# EC_Shield.net
KiCad netlist of a schematic drawn in EAGLE
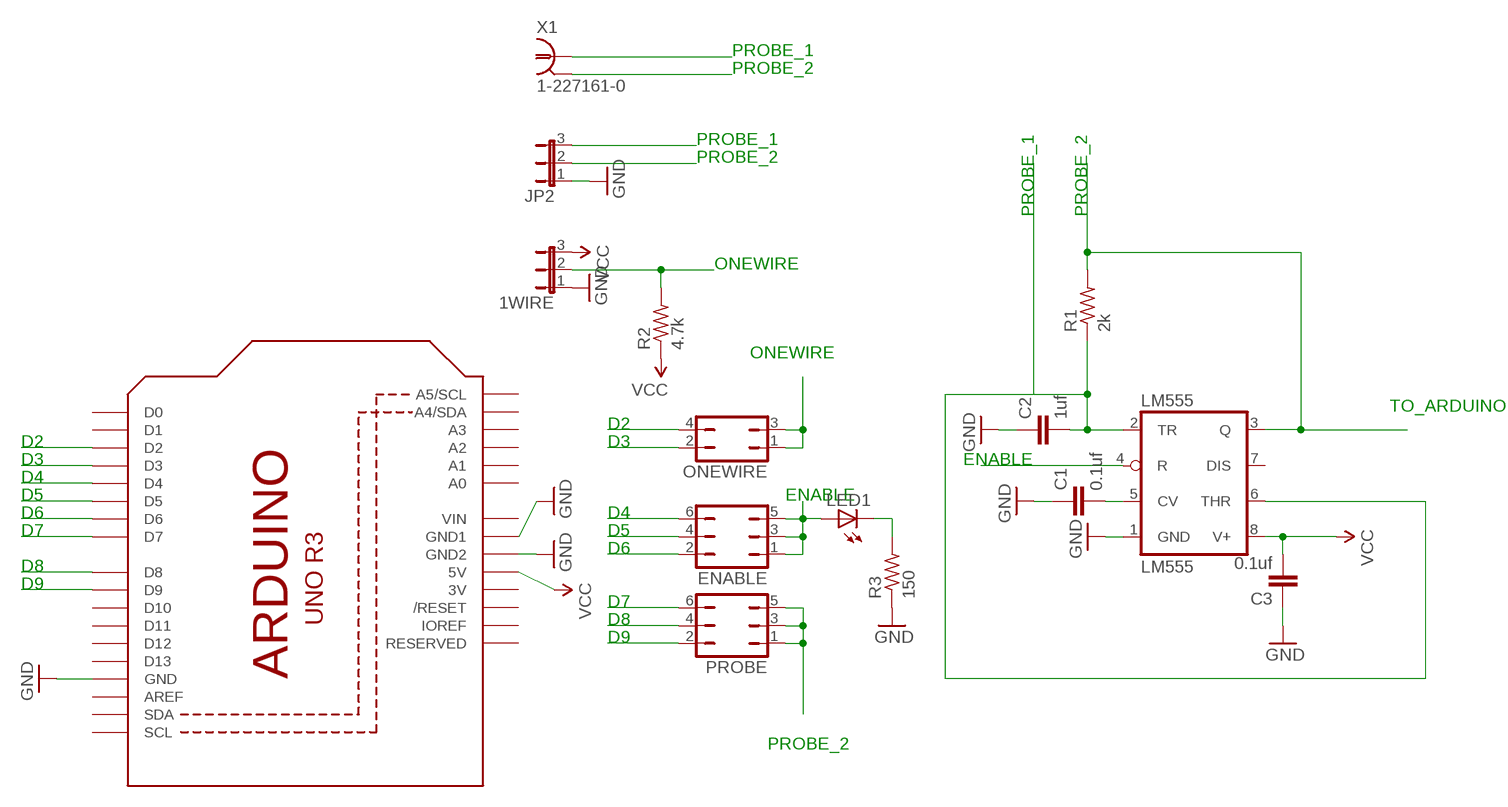
[diagram p0: schematic, sheet 1]

(export (version "E")
  (design (tool "Eeschema 10.0.6"))
  (components
    (comp (ref "1WIRE")
      (value "JP2E")
      (footprint "eagle-import:JP2")
      (libsource (lib "eagle-import") (part "JP2E"))
    )
    (comp (ref "C1")
      (value "0.1uf")
      (footprint "eagle-import:C0603")
      (libsource (lib "eagle-import") (part "C-EUC0603"))
    )
    (comp (ref "C2")
      (value "1uf")
      (footprint "eagle-import:C0603")
      (libsource (lib "eagle-import") (part "C-EUC0603"))
    )
    (comp (ref "C3")
      (value "0.1uf")
      (footprint "eagle-import:C0603")
      (libsource (lib "eagle-import") (part "C-EUC0603"))
    )
    (comp (ref "ENABLE")
      (value "JP3Q")
      (footprint "eagle-import:JP3Q")
      (libsource (lib "eagle-import") (part "JP3Q"))
    )
    (comp (ref "JP2")
      (value "JP2E")
      (footprint "eagle-import:JP2")
      (libsource (lib "eagle-import") (part "JP2E"))
    )
    (comp (ref "LED1")
      (value "LED0603")
      (footprint "eagle-import:LED-0603")
      (libsource (lib "eagle-import") (part "LED0603"))
    )
    (comp (ref "LM555")
      (value "LM555")
      (footprint "eagle-import:SO08")
      (libsource (lib "eagle-import") (part "555DLM"))
    )
    (comp (ref "ONEWIRE")
      (value "JP2Q")
      (footprint "eagle-import:JP2Q")
      (libsource (lib "eagle-import") (part "JP2Q"))
    )
    (comp (ref "PROBE")
      (value "JP3Q")
      (footprint "eagle-import:JP3Q")
      (libsource (lib "eagle-import") (part "JP3Q"))
    )
    (comp (ref "R1")
      (value "2k")
      (footprint "eagle-import:R0603")
      (libsource (lib "eagle-import") (part "R-US_R0603"))
    )
    (comp (ref "R2")
      (value "4.7k")
      (footprint "eagle-import:R0603")
      (libsource (lib "eagle-import") (part "R-US_R0603"))
    )
    (comp (ref "R3")
      (value "150")
      (footprint "eagle-import:R0603")
      (libsource (lib "eagle-import") (part "R-US_R0603"))
    )
    (comp (ref "U2")
      (value "ARDUINOR3-DIMENSION")
      (footprint "eagle-import:ARDUINOR3")
      (libsource (lib "eagle-import") (part "ARDUINOR3-DIMENSION"))
    )
    (comp (ref "X1")
      (value "1-227161-0")
      (footprint "eagle-import:AMP_227161")
      (libsource (lib "eagle-import") (part "?2271611--0"))
    )
  )
  (nets
    (net (code "1") (name "/3V") (class "Default")
      (node (ref "U2") (pin "3V") (pinfunction "3V_3V") (pintype "power_in"))
    )
    (net (code "2") (name "/D2") (class "Default")
      (node (ref "ONEWIRE") (pin "4") (pinfunction "4_4") (pintype "passive"))
      (node (ref "U2") (pin "D2") (pinfunction "D2_D2") (pintype "bidirectional"))
    )
    (net (code "3") (name "/D3") (class "Default")
      (node (ref "ONEWIRE") (pin "2") (pinfunction "2_2") (pintype "passive"))
      (node (ref "U2") (pin "D3") (pinfunction "D3_D3") (pintype "bidirectional"))
    )
    (net (code "4") (name "/D4") (class "Default")
      (node (ref "ENABLE") (pin "6") (pinfunction "6_6") (pintype "passive"))
      (node (ref "U2") (pin "D4") (pinfunction "D4_D4") (pintype "bidirectional"))
    )
    (net (code "5") (name "/D5") (class "Default")
      (node (ref "ENABLE") (pin "4") (pinfunction "4_4") (pintype "passive"))
      (node (ref "U2") (pin "D5") (pinfunction "D5_D5") (pintype "bidirectional"))
    )
    (net (code "6") (name "/D6") (class "Default")
      (node (ref "ENABLE") (pin "2") (pinfunction "2_2") (pintype "passive"))
      (node (ref "U2") (pin "D6") (pinfunction "D6_D6") (pintype "bidirectional"))
    )
    (net (code "7") (name "/D7") (class "Default")
      (node (ref "PROBE") (pin "6") (pinfunction "6_6") (pintype "passive"))
      (node (ref "U2") (pin "D7") (pinfunction "D7_D7") (pintype "bidirectional"))
    )
    (net (code "8") (name "/D8") (class "Default")
      (node (ref "PROBE") (pin "4") (pinfunction "4_4") (pintype "passive"))
      (node (ref "U2") (pin "D8") (pinfunction "D8_D8") (pintype "bidirectional"))
    )
    (net (code "9") (name "/D9") (class "Default")
      (node (ref "PROBE") (pin "2") (pinfunction "2_2") (pintype "passive"))
      (node (ref "U2") (pin "D9") (pinfunction "D9_D9") (pintype "bidirectional"))
    )
    (net (code "10") (name "/ENABLE") (class "Default")
      (node (ref "ENABLE") (pin "1") (pinfunction "1_1") (pintype "passive"))
      (node (ref "ENABLE") (pin "3") (pinfunction "3_3") (pintype "passive"))
      (node (ref "ENABLE") (pin "5") (pinfunction "5_5") (pintype "passive"))
      (node (ref "LED1") (pin "A") (pinfunction "A_A") (pintype "passive"))
      (node (ref "LM555") (pin "4") (pinfunction "R_4") (pintype "input"))
    )
    (net (code "11") (name "/ONEWIRE") (class "Default")
      (node (ref "1WIRE") (pin "2") (pinfunction "2_2") (pintype "passive"))
      (node (ref "ONEWIRE") (pin "1") (pinfunction "1_1") (pintype "passive"))
      (node (ref "ONEWIRE") (pin "3") (pinfunction "3_3") (pintype "passive"))
      (node (ref "R2") (pin "2") (pinfunction "2_2") (pintype "passive"))
    )
    (net (code "12") (name "/PROBE_1") (class "Default")
      (node (ref "C2") (pin "2") (pinfunction "2_2") (pintype "passive"))
      (node (ref "JP2") (pin "3") (pinfunction "3_3") (pintype "passive"))
      (node (ref "LM555") (pin "2") (pinfunction "TR_2") (pintype "input"))
      (node (ref "LM555") (pin "6") (pinfunction "THR_6") (pintype "input"))
      (node (ref "R1") (pin "1") (pinfunction "1_1") (pintype "passive"))
      (node (ref "X1") (pin "1") (pinfunction "1_1") (pintype "passive"))
    )
    (net (code "13") (name "/PROBE_2") (class "Default")
      (node (ref "JP2") (pin "2") (pinfunction "2_2") (pintype "passive"))
      (node (ref "LM555") (pin "3") (pinfunction "Q_3") (pintype "output"))
      (node (ref "PROBE") (pin "1") (pinfunction "1_1") (pintype "passive"))
      (node (ref "PROBE") (pin "3") (pinfunction "3_3") (pintype "passive"))
      (node (ref "PROBE") (pin "5") (pinfunction "5_5") (pintype "passive"))
      (node (ref "R1") (pin "2") (pinfunction "2_2") (pintype "passive"))
      (node (ref "X1") (pin "2") (pinfunction "GND_2") (pintype "power_in"))
    )
    (net (code "14") (name "/VIN") (class "Default")
      (node (ref "U2") (pin "VIN") (pinfunction "VIN_VIN") (pintype "power_in"))
    )
    (net (code "15") (name "GND") (class "Default")
      (node (ref "1WIRE") (pin "1") (pinfunction "1_1") (pintype "passive"))
      (node (ref "C1") (pin "1") (pinfunction "1_1") (pintype "passive"))
      (node (ref "C2") (pin "1") (pinfunction "1_1") (pintype "passive"))
      (node (ref "C3") (pin "1") (pinfunction "1_1") (pintype "passive"))
      (node (ref "JP2") (pin "1") (pinfunction "1_1") (pintype "passive"))
      (node (ref "LM555") (pin "1") (pinfunction "GND_1") (pintype "power_in"))
      (node (ref "R3") (pin "1") (pinfunction "1_1") (pintype "passive"))
      (node (ref "U2") (pin "GND") (pinfunction "GND_GND") (pintype "power_in"))
      (node (ref "U2") (pin "GND1") (pinfunction "GND1_GND1") (pintype "power_in"))
      (node (ref "U2") (pin "GND2") (pinfunction "GND2_GND2") (pintype "power_in"))
    )
    (net (code "16") (name "Net-(LED1-PadC)") (class "Default")
      (node (ref "LED1") (pin "C") (pinfunction "C_C") (pintype "passive"))
      (node (ref "R3") (pin "2") (pinfunction "2_2") (pintype "passive"))
    )
    (net (code "17") (name "Net-(LM555-CV)") (class "Default")
      (node (ref "C1") (pin "2") (pinfunction "2_2") (pintype "passive"))
      (node (ref "LM555") (pin "5") (pinfunction "CV_5") (pintype "input"))
    )
    (net (code "18") (name "VCC") (class "Default")
      (node (ref "1WIRE") (pin "3") (pinfunction "3_3") (pintype "passive"))
      (node (ref "C3") (pin "2") (pinfunction "2_2") (pintype "passive"))
      (node (ref "LM555") (pin "8") (pinfunction "V+_8") (pintype "power_in"))
      (node (ref "R2") (pin "1") (pinfunction "1_1") (pintype "passive"))
      (node (ref "U2") (pin "5V") (pinfunction "5V_5V") (pintype "power_in"))
    )
    (net (code "19") (name "unconnected-(LM555-DIS-Pad7)") (class "Default")
      (node (ref "LM555") (pin "7") (pinfunction "DIS_7") (pintype "input"))
    )
    (net (code "20") (name "unconnected-(U2-A4{slash}SDA-PadA4)") (class "Default")
      (node (ref "U2") (pin "A4") (pinfunction "A4/SDA_A4") (pintype "bidirectional"))
    )
    (net (code "21") (name "unconnected-(U2-A5{slash}SCL-PadA5)") (class "Default")
      (node (ref "U2") (pin "A5") (pinfunction "A5/SCL_A5") (pintype "bidirectional"))
    )
    (net (code "22") (name "unconnected-(U2-PadA0)") (class "Default")
      (node (ref "U2") (pin "A0") (pinfunction "A0_A0") (pintype "bidirectional"))
    )
    (net (code "23") (name "unconnected-(U2-PadA1)") (class "Default")
      (node (ref "U2") (pin "A1") (pinfunction "A1_A1") (pintype "bidirectional"))
    )
    (net (code "24") (name "unconnected-(U2-PadA2)") (class "Default")
      (node (ref "U2") (pin "A2") (pinfunction "A2_A2") (pintype "bidirectional"))
    )
    (net (code "25") (name "unconnected-(U2-PadA3)") (class "Default")
      (node (ref "U2") (pin "A3") (pinfunction "A3_A3") (pintype "bidirectional"))
    )
    (net (code "26") (name "unconnected-(U2-PadAREF)") (class "Default")
      (node (ref "U2") (pin "AREF") (pinfunction "AREF_AREF") (pintype "bidirectional"))
    )
    (net (code "27") (name "unconnected-(U2-PadD0)") (class "Default")
      (node (ref "U2") (pin "D0") (pinfunction "D0_D0") (pintype "bidirectional"))
    )
    (net (code "28") (name "unconnected-(U2-PadD1)") (class "Default")
      (node (ref "U2") (pin "D1") (pinfunction "D1_D1") (pintype "bidirectional"))
    )
    (net (code "29") (name "unconnected-(U2-PadD10)") (class "Default")
      (node (ref "U2") (pin "D10") (pinfunction "D10_D10") (pintype "bidirectional"))
    )
    (net (code "30") (name "unconnected-(U2-PadD11)") (class "Default")
      (node (ref "U2") (pin "D11") (pinfunction "D11_D11") (pintype "bidirectional"))
    )
    (net (code "31") (name "unconnected-(U2-PadD12)") (class "Default")
      (node (ref "U2") (pin "D12") (pinfunction "D12_D12") (pintype "bidirectional"))
    )
    (net (code "32") (name "unconnected-(U2-PadD13)") (class "Default")
      (node (ref "U2") (pin "D13") (pinfunction "D13_D13") (pintype "bidirectional"))
    )
    (net (code "33") (name "unconnected-(U2-PadIOREF)") (class "Default")
      (node (ref "U2") (pin "IOREF") (pinfunction "IOREF_IOREF") (pintype "output"))
    )
    (net (code "34") (name "unconnected-(U2-PadRESERVED)") (class "Default")
      (node (ref "U2") (pin "RESERVED") (pinfunction "RESERVED_RESERVED") (pintype "no_connect"))
    )
    (net (code "35") (name "unconnected-(U2-PadSCL)") (class "Default")
      (node (ref "U2") (pin "SCL") (pinfunction "SCL_SCL") (pintype "bidirectional"))
    )
    (net (code "36") (name "unconnected-(U2-PadSDA)") (class "Default")
      (node (ref "U2") (pin "SDA") (pinfunction "SDA_SDA") (pintype "bidirectional"))
    )
    (net (code "37") (name "unconnected-(U2-{slash}RESET-PadRESET)") (class "Default")
      (node (ref "U2") (pin "RESET") (pinfunction "/RESET_RESET") (pintype "bidirectional"))
    )
  )
)
